# pca10036_sheet3_buttons_and_leds.net
KiCad netlist of a schematic drawn in Altium Designer
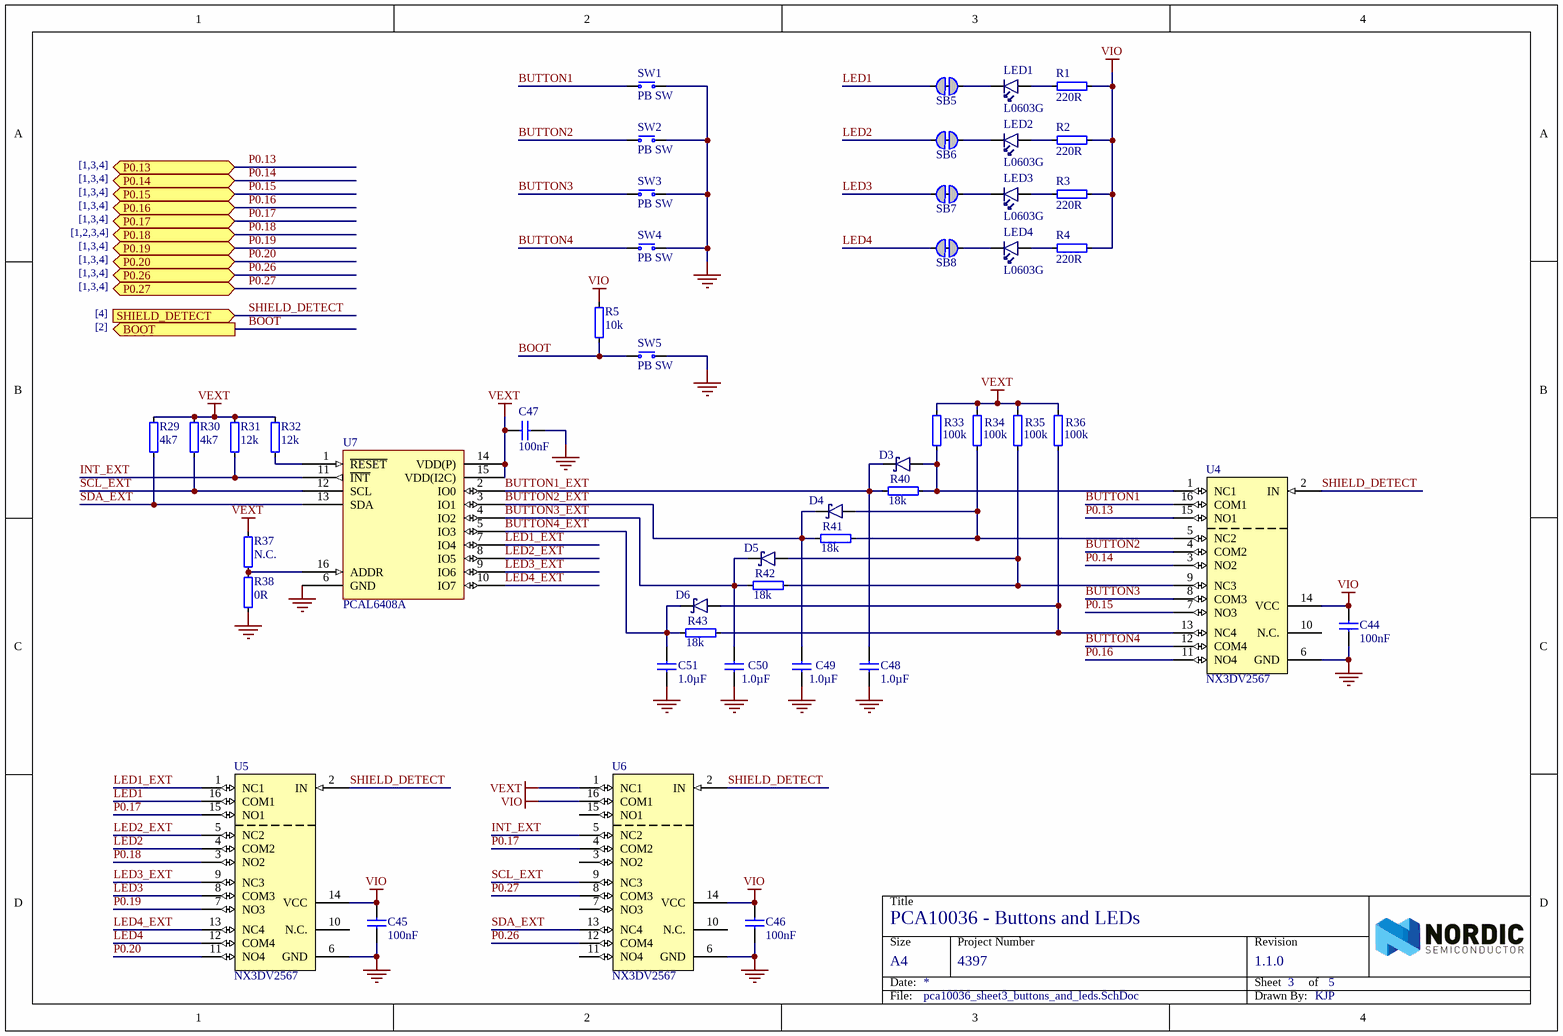
[diagram p0: pca10036_sheet3_buttons_and_leds.SchDoc]

(export (version "E")
  (design (tool "Eeschema 10.0.6"))
  (components
    (comp (ref "C44")
      (value "100nF")
      (footprint "CAPC1005X04L")
      (description "Capacitor, X7R, ±10%")
      (fields (field (name "PART NUMBER") "C0402-100n") (field (name "PUBLISHER") "Nordic Semiconductor"))
      (libsource (lib "Nordic Passive DB") (part "CAP"))
    )
    (comp (ref "C45")
      (value "100nF")
      (footprint "CAPC1005X04L")
      (description "Capacitor, X7R, ±10%")
      (fields (field (name "PART NUMBER") "C0402-100n") (field (name "PUBLISHER") "Nordic Semiconductor"))
      (libsource (lib "Nordic Passive DB") (part "CAP"))
    )
    (comp (ref "C46")
      (value "100nF")
      (footprint "CAPC1005X04L")
      (description "Capacitor, X7R, ±10%")
      (fields (field (name "PART NUMBER") "C0402-100n") (field (name "PUBLISHER") "Nordic Semiconductor"))
      (libsource (lib "Nordic Passive DB") (part "CAP"))
    )
    (comp (ref "C47")
      (value "100nF")
      (footprint "CAPC1005X04L")
      (description "Capacitor, X7R, ±10%")
      (fields (field (name "PART NUMBER") "C0402-100n") (field (name "PUBLISHER") "Nordic Semiconductor"))
      (libsource (lib "Nordic Passive DB") (part "CAP"))
    )
    (comp (ref "C48")
      (value "1.0µF")
      (footprint "CAPC1005X04L")
      (description "Capacitor, X5R, ±5%")
      (fields (field (name "PART NUMBER") "C0402-1µ0") (field (name "PUBLISHER") "Nordic Semiconductor"))
      (libsource (lib "Nordic Passive DB") (part "CAP"))
    )
    (comp (ref "C49")
      (value "1.0µF")
      (footprint "CAPC1005X04L")
      (description "Capacitor, X5R, ±5%")
      (fields (field (name "PART NUMBER") "C0402-1µ0") (field (name "PUBLISHER") "Nordic Semiconductor"))
      (libsource (lib "Nordic Passive DB") (part "CAP"))
    )
    (comp (ref "C50")
      (value "1.0µF")
      (footprint "CAPC1005X04L")
      (description "Capacitor, X5R, ±5%")
      (fields (field (name "PART NUMBER") "C0402-1µ0") (field (name "PUBLISHER") "Nordic Semiconductor"))
      (libsource (lib "Nordic Passive DB") (part "CAP"))
    )
    (comp (ref "C51")
      (value "1.0µF")
      (footprint "CAPC1005X04L")
      (description "Capacitor, X5R, ±5%")
      (fields (field (name "PART NUMBER") "C0402-1µ0") (field (name "PUBLISHER") "Nordic Semiconductor"))
      (libsource (lib "Nordic Passive DB") (part "CAP"))
    )
    (comp (ref "D3")
      (value "1PS79SB30.115")
      (footprint "SOD-523")
      (description "Diode Schottky Vf=0.38, Vr=40V, If=200mA, Ir=500nA")
      (fields (field (name "MANUFACTURER") "NXP") (field (name "PUBLISHER") "Nordic Semiconductor"))
      (libsource (lib "Nordic Discrete DB") (part "D{colon}SCHOTTKY"))
    )
    (comp (ref "D4")
      (value "1PS79SB30.115")
      (footprint "SOD-523")
      (description "Diode Schottky Vf=0.38, Vr=40V, If=200mA, Ir=500nA")
      (fields (field (name "MANUFACTURER") "NXP") (field (name "PUBLISHER") "Nordic Semiconductor"))
      (libsource (lib "Nordic Discrete DB") (part "D{colon}SCHOTTKY"))
    )
    (comp (ref "D5")
      (value "1PS79SB30.115")
      (footprint "SOD-523")
      (description "Diode Schottky Vf=0.38, Vr=40V, If=200mA, Ir=500nA")
      (fields (field (name "MANUFACTURER") "NXP") (field (name "PUBLISHER") "Nordic Semiconductor"))
      (libsource (lib "Nordic Discrete DB") (part "D{colon}SCHOTTKY"))
    )
    (comp (ref "D6")
      (value "1PS79SB30.115")
      (footprint "SOD-523")
      (description "Diode Schottky Vf=0.38, Vr=40V, If=200mA, Ir=500nA")
      (fields (field (name "MANUFACTURER") "NXP") (field (name "PUBLISHER") "Nordic Semiconductor"))
      (libsource (lib "Nordic Discrete DB") (part "D{colon}SCHOTTKY"))
    )
    (comp (ref "LED1")
      (value "L0603G")
      (footprint "LED_0603_G")
      (description "LED 0603, EL19-21SYGC")
      (fields
        (field (name "PART NUMBER") "EL19-21SYGC")
        (field (name "MANUFACTURER") "Everlight")
        (field (name "PUBLISHER") "Nordic Semiconductor")
      )
      (libsource (lib "Nordic Discrete DB") (part "D{colon}LED"))
    )
    (comp (ref "LED2")
      (value "L0603G")
      (footprint "LED_0603_G")
      (description "LED 0603, EL19-21SYGC")
      (fields
        (field (name "PART NUMBER") "EL19-21SYGC")
        (field (name "MANUFACTURER") "Everlight")
        (field (name "PUBLISHER") "Nordic Semiconductor")
      )
      (libsource (lib "Nordic Discrete DB") (part "D{colon}LED"))
    )
    (comp (ref "LED3")
      (value "L0603G")
      (footprint "LED_0603_G")
      (description "LED 0603, EL19-21SYGC")
      (fields
        (field (name "PART NUMBER") "EL19-21SYGC")
        (field (name "MANUFACTURER") "Everlight")
        (field (name "PUBLISHER") "Nordic Semiconductor")
      )
      (libsource (lib "Nordic Discrete DB") (part "D{colon}LED"))
    )
    (comp (ref "LED4")
      (value "L0603G")
      (footprint "LED_0603_G")
      (description "LED 0603, EL19-21SYGC")
      (fields
        (field (name "PART NUMBER") "EL19-21SYGC")
        (field (name "MANUFACTURER") "Everlight")
        (field (name "PUBLISHER") "Nordic Semiconductor")
      )
      (libsource (lib "Nordic Discrete DB") (part "D{colon}LED"))
    )
    (comp (ref "R1")
      (value "220R")
      (footprint "RESC1005X04L")
      (description "Resistor, ±1%, 0.063W")
      (fields (field (name "PART NUMBER") "R0402-220") (field (name "PUBLISHER") "Nordic Semiconductor"))
      (libsource (lib "Nordic Passive DB") (part "RES_1"))
    )
    (comp (ref "R2")
      (value "220R")
      (footprint "RESC1005X04L")
      (description "Resistor, ±1%, 0.063W")
      (fields (field (name "PART NUMBER") "R0402-220") (field (name "PUBLISHER") "Nordic Semiconductor"))
      (libsource (lib "Nordic Passive DB") (part "RES_1"))
    )
    (comp (ref "R3")
      (value "220R")
      (footprint "RESC1005X04L")
      (description "Resistor, ±1%, 0.063W")
      (fields (field (name "PART NUMBER") "R0402-220") (field (name "PUBLISHER") "Nordic Semiconductor"))
      (libsource (lib "Nordic Passive DB") (part "RES_1"))
    )
    (comp (ref "R4")
      (value "220R")
      (footprint "RESC1005X04L")
      (description "Resistor, ±1%, 0.063W")
      (fields (field (name "PART NUMBER") "R0402-220") (field (name "PUBLISHER") "Nordic Semiconductor"))
      (libsource (lib "Nordic Passive DB") (part "RES_1"))
    )
    (comp (ref "R5")
      (value "10k")
      (footprint "RESC1005X04L")
      (description "Resistor, ±1%, 0.063W")
      (fields (field (name "PART NUMBER") "R0402-10k") (field (name "PUBLISHER") "Nordic Semiconductor"))
      (libsource (lib "Nordic Passive DB") (part "RES_1"))
    )
    (comp (ref "R29")
      (value "4k7")
      (footprint "RESC1005X04L")
      (description "Resistor, ±1%, 0.063W")
      (fields (field (name "PART NUMBER") "R0402-4k7") (field (name "PUBLISHER") "Nordic Semiconductor"))
      (libsource (lib "Nordic Passive DB") (part "RES_1"))
    )
    (comp (ref "R30")
      (value "4k7")
      (footprint "RESC1005X04L")
      (description "Resistor, ±1%, 0.063W")
      (fields (field (name "PART NUMBER") "R0402-4k7") (field (name "PUBLISHER") "Nordic Semiconductor"))
      (libsource (lib "Nordic Passive DB") (part "RES_1"))
    )
    (comp (ref "R31")
      (value "12k")
      (footprint "RESC1005X04L")
      (description "Resistor, ±1%, 0.063W")
      (fields (field (name "PART NUMBER") "R0402-12k") (field (name "PUBLISHER") "Nordic Semiconductor"))
      (libsource (lib "Nordic Passive DB") (part "RES_1"))
    )
    (comp (ref "R32")
      (value "12k")
      (footprint "RESC1005X04L")
      (description "Resistor, ±1%, 0.063W")
      (fields (field (name "PART NUMBER") "R0402-12k") (field (name "PUBLISHER") "Nordic Semiconductor"))
      (libsource (lib "Nordic Passive DB") (part "RES_1"))
    )
    (comp (ref "R33")
      (value "100k")
      (footprint "RESC1005X04L")
      (description "Resistor, ±1%, 0.063W")
      (fields (field (name "PART NUMBER") "R0402-100k") (field (name "PUBLISHER") "Nordic Semiconductor"))
      (libsource (lib "Nordic Passive DB") (part "RES_1"))
    )
    (comp (ref "R34")
      (value "100k")
      (footprint "RESC1005X04L")
      (description "Resistor, ±1%, 0.063W")
      (fields (field (name "PART NUMBER") "R0402-100k") (field (name "PUBLISHER") "Nordic Semiconductor"))
      (libsource (lib "Nordic Passive DB") (part "RES_1"))
    )
    (comp (ref "R35")
      (value "100k")
      (footprint "RESC1005X04L")
      (description "Resistor, ±1%, 0.063W")
      (fields (field (name "PART NUMBER") "R0402-100k") (field (name "PUBLISHER") "Nordic Semiconductor"))
      (libsource (lib "Nordic Passive DB") (part "RES_1"))
    )
    (comp (ref "R36")
      (value "100k")
      (footprint "RESC1005X04L")
      (description "Resistor, ±1%, 0.063W")
      (fields (field (name "PART NUMBER") "R0402-100k") (field (name "PUBLISHER") "Nordic Semiconductor"))
      (libsource (lib "Nordic Passive DB") (part "RES_1"))
    )
    (comp (ref "R37")
      (value "N.C.")
      (footprint "RESC1005X04L")
      (description "Not mounted")
      (fields (field (name "PART NUMBER") "R0402-N.C.") (field (name "PUBLISHER") "Nordic Semiconductor"))
      (libsource (lib "Nordic Passive DB") (part "RES_1"))
    )
    (comp (ref "R38")
      (value "0R")
      (footprint "RESC1005X04L")
      (description "Resistor, ±5%, 0.063W")
      (fields (field (name "PART NUMBER") "R0402-0R") (field (name "PUBLISHER") "Nordic Semiconductor"))
      (libsource (lib "Nordic Passive DB") (part "RES_1"))
    )
    (comp (ref "R40")
      (value "18k")
      (footprint "RESC1005X04L")
      (description "Resistor, ±1%, 0.063W")
      (fields (field (name "PART NUMBER") "R0402-18k") (field (name "PUBLISHER") "Nordic Semiconductor"))
      (libsource (lib "Nordic Passive DB") (part "RES_1"))
    )
    (comp (ref "R41")
      (value "18k")
      (footprint "RESC1005X04L")
      (description "Resistor, ±1%, 0.063W")
      (fields (field (name "PART NUMBER") "R0402-18k") (field (name "PUBLISHER") "Nordic Semiconductor"))
      (libsource (lib "Nordic Passive DB") (part "RES_1"))
    )
    (comp (ref "R42")
      (value "18k")
      (footprint "RESC1005X04L")
      (description "Resistor, ±1%, 0.063W")
      (fields (field (name "PART NUMBER") "R0402-18k") (field (name "PUBLISHER") "Nordic Semiconductor"))
      (libsource (lib "Nordic Passive DB") (part "RES_1"))
    )
    (comp (ref "R43")
      (value "18k")
      (footprint "RESC1005X04L")
      (description "Resistor, ±1%, 0.063W")
      (fields (field (name "PART NUMBER") "R0402-18k") (field (name "PUBLISHER") "Nordic Semiconductor"))
      (libsource (lib "Nordic Passive DB") (part "RES_1"))
    )
    (comp (ref "SB5")
      (value "Solderbridge")
      (footprint "Solderbridge_Shorted")
      (description "Shorted Solderbridge")
      (fields
        (field (name "PART NUMBER") "Solderbridge Shorted")
        (field (name "PUBLISHER") "Nordic Semiconductor")
      )
      (libsource (lib "Nordic Passive DB") (part "SOLDERBRIDGE_SHORTED"))
    )
    (comp (ref "SB6")
      (value "Solderbridge")
      (footprint "Solderbridge_Shorted")
      (description "Shorted Solderbridge")
      (fields
        (field (name "PART NUMBER") "Solderbridge Shorted")
        (field (name "PUBLISHER") "Nordic Semiconductor")
      )
      (libsource (lib "Nordic Passive DB") (part "SOLDERBRIDGE_SHORTED"))
    )
    (comp (ref "SB7")
      (value "Solderbridge")
      (footprint "Solderbridge_Shorted")
      (description "Shorted Solderbridge")
      (fields
        (field (name "PART NUMBER") "Solderbridge Shorted")
        (field (name "PUBLISHER") "Nordic Semiconductor")
      )
      (libsource (lib "Nordic Passive DB") (part "SOLDERBRIDGE_SHORTED"))
    )
    (comp (ref "SB8")
      (value "Solderbridge")
      (footprint "Solderbridge_Shorted")
      (description "Shorted Solderbridge")
      (fields
        (field (name "PART NUMBER") "Solderbridge Shorted")
        (field (name "PUBLISHER") "Nordic Semiconductor")
      )
      (libsource (lib "Nordic Passive DB") (part "SOLDERBRIDGE_SHORTED"))
    )
    (comp (ref "SW1")
      (value "PB SW")
      (footprint "ALPS_SKHUxxx010_WO_GND")
      (description "ALPS - SKHUALE010 - Tactile Switch, SPNO, SMD, 6.5x6.2x2.5mm")
      (fields
        (field (name "PART NUMBER") "ALPS_SKHUALE010")
        (field (name "MANUFACTURER") "Alps")
        (field (name "PUBLISHER") "Nordic Semiconductor")
      )
      (libsource (lib "Nordic Discrete DB") (part "SW-PB"))
    )
    (comp (ref "SW2")
      (value "PB SW")
      (footprint "ALPS_SKHUxxx010_WO_GND")
      (description "ALPS - SKHUALE010 - Tactile Switch, SPNO, SMD, 6.5x6.2x2.5mm")
      (fields
        (field (name "PART NUMBER") "ALPS_SKHUALE010")
        (field (name "MANUFACTURER") "Alps")
        (field (name "PUBLISHER") "Nordic Semiconductor")
      )
      (libsource (lib "Nordic Discrete DB") (part "SW-PB"))
    )
    (comp (ref "SW3")
      (value "PB SW")
      (footprint "ALPS_SKHUxxx010_WO_GND")
      (description "ALPS - SKHUALE010 - Tactile Switch, SPNO, SMD, 6.5x6.2x2.5mm")
      (fields
        (field (name "PART NUMBER") "ALPS_SKHUALE010")
        (field (name "MANUFACTURER") "Alps")
        (field (name "PUBLISHER") "Nordic Semiconductor")
      )
      (libsource (lib "Nordic Discrete DB") (part "SW-PB"))
    )
    (comp (ref "SW4")
      (value "PB SW")
      (footprint "ALPS_SKHUxxx010_WO_GND")
      (description "ALPS - SKHUALE010 - Tactile Switch, SPNO, SMD, 6.5x6.2x2.5mm")
      (fields
        (field (name "PART NUMBER") "ALPS_SKHUALE010")
        (field (name "MANUFACTURER") "Alps")
        (field (name "PUBLISHER") "Nordic Semiconductor")
      )
      (libsource (lib "Nordic Discrete DB") (part "SW-PB"))
    )
    (comp (ref "SW5")
      (value "PB SW")
      (footprint "ALPS_SKHUxxx010_WO_GND")
      (description "ALPS - SKHUALE010 - Tactile Switch, SPNO, SMD, 6.5x6.2x2.5mm")
      (fields
        (field (name "PART NUMBER") "ALPS_SKHUALE010")
        (field (name "MANUFACTURER") "Alps")
        (field (name "PUBLISHER") "Nordic Semiconductor")
      )
      (libsource (lib "Nordic Discrete DB") (part "SW-PB"))
    )
    (comp (ref "U4")
      (value "NX3DV2567")
      (footprint "XQFN40P180X260X50-16N")
      (description "Low-ohmic four-pole double-throw analog switch")
      (fields
        (field (name "PART NUMBER") "NX3DV2567GU")
        (field (name "MANUFACTURER") "NXP Semiconductors")
        (field (name "PUBLISHER") "Nordic Semiconductor")
      )
      (libsource (lib "Nordic Active DB") (part "NX3DV2567"))
    )
    (comp (ref "U5")
      (value "NX3DV2567")
      (footprint "XQFN40P180X260X50-16N")
      (description "Low-ohmic four-pole double-throw analog switch")
      (fields
        (field (name "PART NUMBER") "NX3DV2567GU")
        (field (name "MANUFACTURER") "NXP Semiconductors")
        (field (name "PUBLISHER") "Nordic Semiconductor")
      )
      (libsource (lib "Nordic Active DB") (part "NX3DV2567"))
    )
    (comp (ref "U6")
      (value "NX3DV2567")
      (footprint "XQFN40P180X260X50-16N")
      (description "Low-ohmic four-pole double-throw analog switch")
      (fields
        (field (name "PART NUMBER") "NX3DV2567GU")
        (field (name "MANUFACTURER") "NXP Semiconductors")
        (field (name "PUBLISHER") "Nordic Semiconductor")
      )
      (libsource (lib "Nordic Active DB") (part "NX3DV2567"))
    )
    (comp (ref "U7")
      (value "PCAL6408A")
      (footprint "XQFN40P180X260X50-16N")
      (description "8-bit I2C-bus I/O expander with interrupt output")
      (fields
        (field (name "PART NUMBER") "PCAL6408AHK")
        (field (name "MANUFACTURER") "NXP Semiconductors")
        (field (name "PUBLISHER") "Nordic Semiconductor")
      )
      (libsource (lib "Nordic Active DB") (part "PCAL6408AHK"))
    )
  )
  (nets
    (net (code "1") (name "/BOOT") (class "Default")
      (node (ref "R5") (pin "1") (pinfunction "1_1") (pintype "passive"))
      (node (ref "SW5") (pin "1") (pinfunction "N.O_1") (pintype "passive"))
    )
    (net (code "2") (name "/BUTTON1") (class "Default")
      (node (ref "SW1") (pin "1") (pinfunction "N.O_1") (pintype "passive"))
      (node (ref "U4") (pin "16") (pinfunction "COM1_16") (pintype "bidirectional"))
    )
    (net (code "3") (name "/BUTTON1_EXT") (class "Default")
      (node (ref "C48") (pin "1") (pinfunction "1_1") (pintype "passive"))
      (node (ref "D3") (pin "3") (pinfunction "C_3") (pintype "passive"))
      (node (ref "R40") (pin "1") (pinfunction "1_1") (pintype "passive"))
      (node (ref "U7") (pin "2") (pinfunction "IO0_2") (pintype "bidirectional"))
    )
    (net (code "4") (name "/BUTTON2") (class "Default")
      (node (ref "SW2") (pin "1") (pinfunction "N.O_1") (pintype "passive"))
      (node (ref "U4") (pin "4") (pinfunction "COM2_4") (pintype "bidirectional"))
    )
    (net (code "5") (name "/BUTTON2_EXT") (class "Default")
      (node (ref "C49") (pin "2") (pinfunction "2_2") (pintype "passive"))
      (node (ref "D4") (pin "3") (pinfunction "C_3") (pintype "passive"))
      (node (ref "R41") (pin "1") (pinfunction "1_1") (pintype "passive"))
      (node (ref "U7") (pin "3") (pinfunction "IO1_3") (pintype "bidirectional"))
    )
    (net (code "6") (name "/BUTTON3") (class "Default")
      (node (ref "SW3") (pin "1") (pinfunction "N.O_1") (pintype "passive"))
      (node (ref "U4") (pin "8") (pinfunction "COM3_8") (pintype "bidirectional"))
    )
    (net (code "7") (name "/BUTTON3_EXT") (class "Default")
      (node (ref "C50") (pin "2") (pinfunction "2_2") (pintype "passive"))
      (node (ref "D5") (pin "3") (pinfunction "C_3") (pintype "passive"))
      (node (ref "R42") (pin "1") (pinfunction "1_1") (pintype "passive"))
      (node (ref "U7") (pin "4") (pinfunction "IO2_4") (pintype "bidirectional"))
    )
    (net (code "8") (name "/BUTTON4") (class "Default")
      (node (ref "SW4") (pin "1") (pinfunction "N.O_1") (pintype "passive"))
      (node (ref "U4") (pin "12") (pinfunction "COM4_12") (pintype "bidirectional"))
    )
    (net (code "9") (name "/BUTTON4_EXT") (class "Default")
      (node (ref "C51") (pin "1") (pinfunction "1_1") (pintype "passive"))
      (node (ref "D6") (pin "3") (pinfunction "C_3") (pintype "passive"))
      (node (ref "R43") (pin "1") (pinfunction "1_1") (pintype "passive"))
      (node (ref "U7") (pin "5") (pinfunction "IO3_5") (pintype "bidirectional"))
    )
    (net (code "10") (name "/INT_EXT") (class "Default")
      (node (ref "R31") (pin "1") (pinfunction "1_1") (pintype "passive"))
      (node (ref "U6") (pin "5") (pinfunction "NC2_5") (pintype "bidirectional"))
      (node (ref "U7") (pin "11") (pinfunction "~{INT}_11") (pintype "output"))
    )
    (net (code "11") (name "/LED1") (class "Default")
      (node (ref "SB5") (pin "1") (pinfunction "0_1") (pintype "passive"))
      (node (ref "U5") (pin "16") (pinfunction "COM1_16") (pintype "bidirectional"))
    )
    (net (code "12") (name "/LED1_EXT") (class "Default")
      (node (ref "U5") (pin "1") (pinfunction "NC1_1") (pintype "bidirectional"))
      (node (ref "U7") (pin "7") (pinfunction "IO4_7") (pintype "bidirectional"))
    )
    (net (code "13") (name "/LED2") (class "Default")
      (node (ref "SB6") (pin "1") (pinfunction "0_1") (pintype "passive"))
      (node (ref "U5") (pin "4") (pinfunction "COM2_4") (pintype "bidirectional"))
    )
    (net (code "14") (name "/LED2_EXT") (class "Default")
      (node (ref "U5") (pin "5") (pinfunction "NC2_5") (pintype "bidirectional"))
      (node (ref "U7") (pin "8") (pinfunction "IO5_8") (pintype "bidirectional"))
    )
    (net (code "15") (name "/LED3") (class "Default")
      (node (ref "SB7") (pin "1") (pinfunction "0_1") (pintype "passive"))
      (node (ref "U5") (pin "8") (pinfunction "COM3_8") (pintype "bidirectional"))
    )
    (net (code "16") (name "/LED3_EXT") (class "Default")
      (node (ref "U5") (pin "9") (pinfunction "NC3_9") (pintype "bidirectional"))
      (node (ref "U7") (pin "9") (pinfunction "IO6_9") (pintype "bidirectional"))
    )
    (net (code "17") (name "/LED4") (class "Default")
      (node (ref "SB8") (pin "1") (pinfunction "0_1") (pintype "passive"))
      (node (ref "U5") (pin "12") (pinfunction "COM4_12") (pintype "bidirectional"))
    )
    (net (code "18") (name "/LED4_EXT") (class "Default")
      (node (ref "U5") (pin "13") (pinfunction "NC4_13") (pintype "bidirectional"))
      (node (ref "U7") (pin "10") (pinfunction "IO7_10") (pintype "bidirectional"))
    )
    (net (code "19") (name "/P0.13") (class "Default")
      (node (ref "U4") (pin "15") (pinfunction "NO1_15") (pintype "bidirectional"))
    )
    (net (code "20") (name "/P0.14") (class "Default")
      (node (ref "U4") (pin "3") (pinfunction "NO2_3") (pintype "bidirectional"))
    )
    (net (code "21") (name "/P0.15") (class "Default")
      (node (ref "U4") (pin "7") (pinfunction "NO3_7") (pintype "bidirectional"))
    )
    (net (code "22") (name "/P0.16") (class "Default")
      (node (ref "U4") (pin "11") (pinfunction "NO4_11") (pintype "bidirectional"))
    )
    (net (code "23") (name "/P0.17") (class "Default")
      (node (ref "U5") (pin "15") (pinfunction "NO1_15") (pintype "bidirectional"))
      (node (ref "U6") (pin "4") (pinfunction "COM2_4") (pintype "bidirectional"))
    )
    (net (code "24") (name "/P0.18") (class "Default")
      (node (ref "U5") (pin "3") (pinfunction "NO2_3") (pintype "bidirectional"))
    )
    (net (code "25") (name "/P0.19") (class "Default")
      (node (ref "U5") (pin "7") (pinfunction "NO3_7") (pintype "bidirectional"))
    )
    (net (code "26") (name "/P0.20") (class "Default")
      (node (ref "U5") (pin "11") (pinfunction "NO4_11") (pintype "bidirectional"))
    )
    (net (code "27") (name "/P0.26") (class "Default")
      (node (ref "U6") (pin "12") (pinfunction "COM4_12") (pintype "bidirectional"))
    )
    (net (code "28") (name "/P0.27") (class "Default")
      (node (ref "U6") (pin "8") (pinfunction "COM3_8") (pintype "bidirectional"))
    )
    (net (code "29") (name "/SCL_EXT") (class "Default")
      (node (ref "R30") (pin "1") (pinfunction "1_1") (pintype "passive"))
      (node (ref "U6") (pin "9") (pinfunction "NC3_9") (pintype "bidirectional"))
      (node (ref "U7") (pin "12") (pinfunction "SCL_12") (pintype "power_in"))
    )
    (net (code "30") (name "/SDA_EXT") (class "Default")
      (node (ref "R29") (pin "1") (pinfunction "1_1") (pintype "passive"))
      (node (ref "U6") (pin "13") (pinfunction "NC4_13") (pintype "bidirectional"))
      (node (ref "U7") (pin "13") (pinfunction "SDA_13") (pintype "passive"))
    )
    (net (code "31") (name "/SHIELD_DETECT") (class "Default")
      (node (ref "U4") (pin "2") (pinfunction "IN_2") (pintype "input"))
      (node (ref "U5") (pin "2") (pinfunction "IN_2") (pintype "input"))
      (node (ref "U6") (pin "2") (pinfunction "IN_2") (pintype "input"))
    )
    (net (code "32") (name "GND") (class "Default")
      (node (ref "C44") (pin "1") (pinfunction "1_1") (pintype "passive"))
      (node (ref "C45") (pin "1") (pinfunction "1_1") (pintype "passive"))
      (node (ref "C46") (pin "1") (pinfunction "1_1") (pintype "passive"))
      (node (ref "C47") (pin "1") (pinfunction "1_1") (pintype "passive"))
      (node (ref "C48") (pin "2") (pinfunction "2_2") (pintype "passive"))
      (node (ref "C49") (pin "1") (pinfunction "1_1") (pintype "passive"))
      (node (ref "C50") (pin "1") (pinfunction "1_1") (pintype "passive"))
      (node (ref "C51") (pin "2") (pinfunction "2_2") (pintype "passive"))
      (node (ref "R38") (pin "1") (pinfunction "1_1") (pintype "passive"))
      (node (ref "SW1") (pin "2") (pinfunction "COM_2") (pintype "passive"))
      (node (ref "SW2") (pin "2") (pinfunction "COM_2") (pintype "passive"))
      (node (ref "SW3") (pin "2") (pinfunction "COM_2") (pintype "passive"))
      (node (ref "SW4") (pin "2") (pinfunction "COM_2") (pintype "passive"))
      (node (ref "SW5") (pin "2") (pinfunction "COM_2") (pintype "passive"))
      (node (ref "U4") (pin "6") (pinfunction "GND_6") (pintype "power_in"))
      (node (ref "U5") (pin "6") (pinfunction "GND_6") (pintype "power_in"))
      (node (ref "U6") (pin "6") (pinfunction "GND_6") (pintype "power_in"))
      (node (ref "U7") (pin "6") (pinfunction "GND_6") (pintype "power_in"))
    )
    (net (code "33") (name "Net-(D3-A)") (class "Default")
      (node (ref "D3") (pin "1") (pinfunction "A_1") (pintype "passive"))
      (node (ref "R33") (pin "1") (pinfunction "1_1") (pintype "passive"))
      (node (ref "R40") (pin "2") (pinfunction "2_2") (pintype "passive"))
      (node (ref "U4") (pin "1") (pinfunction "NC1_1") (pintype "bidirectional"))
    )
    (net (code "34") (name "Net-(D4-A)") (class "Default")
      (node (ref "D4") (pin "1") (pinfunction "A_1") (pintype "passive"))
      (node (ref "R34") (pin "1") (pinfunction "1_1") (pintype "passive"))
      (node (ref "R41") (pin "2") (pinfunction "2_2") (pintype "passive"))
      (node (ref "U4") (pin "5") (pinfunction "NC2_5") (pintype "bidirectional"))
    )
    (net (code "35") (name "Net-(D5-A)") (class "Default")
      (node (ref "D5") (pin "1") (pinfunction "A_1") (pintype "passive"))
      (node (ref "R35") (pin "1") (pinfunction "1_1") (pintype "passive"))
      (node (ref "R42") (pin "2") (pinfunction "2_2") (pintype "passive"))
      (node (ref "U4") (pin "9") (pinfunction "NC3_9") (pintype "bidirectional"))
    )
    (net (code "36") (name "Net-(D6-A)") (class "Default")
      (node (ref "D6") (pin "1") (pinfunction "A_1") (pintype "passive"))
      (node (ref "R36") (pin "1") (pinfunction "1_1") (pintype "passive"))
      (node (ref "R43") (pin "2") (pinfunction "2_2") (pintype "passive"))
      (node (ref "U4") (pin "13") (pinfunction "NC4_13") (pintype "bidirectional"))
    )
    (net (code "37") (name "Net-(LED1-A)") (class "Default")
      (node (ref "LED1") (pin "2") (pinfunction "A_2") (pintype "passive"))
      (node (ref "R1") (pin "1") (pinfunction "1_1") (pintype "passive"))
    )
    (net (code "38") (name "Net-(LED1-C)") (class "Default")
      (node (ref "LED1") (pin "1") (pinfunction "C_1") (pintype "passive"))
      (node (ref "SB5") (pin "2") (pinfunction "1_2") (pintype "passive"))
    )
    (net (code "39") (name "Net-(LED2-A)") (class "Default")
      (node (ref "LED2") (pin "2") (pinfunction "A_2") (pintype "passive"))
      (node (ref "R2") (pin "1") (pinfunction "1_1") (pintype "passive"))
    )
    (net (code "40") (name "Net-(LED2-C)") (class "Default")
      (node (ref "LED2") (pin "1") (pinfunction "C_1") (pintype "passive"))
      (node (ref "SB6") (pin "2") (pinfunction "1_2") (pintype "passive"))
    )
    (net (code "41") (name "Net-(LED3-A)") (class "Default")
      (node (ref "LED3") (pin "2") (pinfunction "A_2") (pintype "passive"))
      (node (ref "R3") (pin "1") (pinfunction "1_1") (pintype "passive"))
    )
    (net (code "42") (name "Net-(LED3-C)") (class "Default")
      (node (ref "LED3") (pin "1") (pinfunction "C_1") (pintype "passive"))
      (node (ref "SB7") (pin "2") (pinfunction "1_2") (pintype "passive"))
    )
    (net (code "43") (name "Net-(LED4-A)") (class "Default")
      (node (ref "LED4") (pin "2") (pinfunction "A_2") (pintype "passive"))
      (node (ref "R4") (pin "1") (pinfunction "1_1") (pintype "passive"))
    )
    (net (code "44") (name "Net-(LED4-C)") (class "Default")
      (node (ref "LED4") (pin "1") (pinfunction "C_1") (pintype "passive"))
      (node (ref "SB8") (pin "2") (pinfunction "1_2") (pintype "passive"))
    )
    (net (code "45") (name "Net-(U7-ADDR)") (class "Default")
      (node (ref "R37") (pin "1") (pinfunction "1_1") (pintype "passive"))
      (node (ref "R38") (pin "2") (pinfunction "2_2") (pintype "passive"))
      (node (ref "U7") (pin "16") (pinfunction "ADDR_16") (pintype "input"))
    )
    (net (code "46") (name "Net-(U7-~{RESET})") (class "Default")
      (node (ref "R32") (pin "1") (pinfunction "1_1") (pintype "passive"))
      (node (ref "U7") (pin "1") (pinfunction "~{RESET}_1") (pintype "input"))
    )
    (net (code "47") (name "VEXT") (class "Default")
      (node (ref "C47") (pin "2") (pinfunction "2_2") (pintype "passive"))
      (node (ref "R29") (pin "2") (pinfunction "2_2") (pintype "passive"))
      (node (ref "R30") (pin "2") (pinfunction "2_2") (pintype "passive"))
      (node (ref "R31") (pin "2") (pinfunction "2_2") (pintype "passive"))
      (node (ref "R32") (pin "2") (pinfunction "2_2") (pintype "passive"))
      (node (ref "R33") (pin "2") (pinfunction "2_2") (pintype "passive"))
      (node (ref "R34") (pin "2") (pinfunction "2_2") (pintype "passive"))
      (node (ref "R35") (pin "2") (pinfunction "2_2") (pintype "passive"))
      (node (ref "R36") (pin "2") (pinfunction "2_2") (pintype "passive"))
      (node (ref "R37") (pin "2") (pinfunction "2_2") (pintype "passive"))
      (node (ref "U6") (pin "1") (pinfunction "NC1_1") (pintype "bidirectional"))
      (node (ref "U7") (pin "14") (pinfunction "VDD(P)_14") (pintype "power_in"))
      (node (ref "U7") (pin "15") (pinfunction "VDD(I2C)_15") (pintype "power_in"))
    )
    (net (code "48") (name "VIO") (class "Default")
      (node (ref "C44") (pin "2") (pinfunction "2_2") (pintype "passive"))
      (node (ref "C45") (pin "2") (pinfunction "2_2") (pintype "passive"))
      (node (ref "C46") (pin "2") (pinfunction "2_2") (pintype "passive"))
      (node (ref "R1") (pin "2") (pinfunction "2_2") (pintype "passive"))
      (node (ref "R2") (pin "2") (pinfunction "2_2") (pintype "passive"))
      (node (ref "R3") (pin "2") (pinfunction "2_2") (pintype "passive"))
      (node (ref "R4") (pin "2") (pinfunction "2_2") (pintype "passive"))
      (node (ref "R5") (pin "2") (pinfunction "2_2") (pintype "passive"))
      (node (ref "U4") (pin "14") (pinfunction "VCC_14") (pintype "power_in"))
      (node (ref "U5") (pin "14") (pinfunction "VCC_14") (pintype "power_in"))
      (node (ref "U6") (pin "14") (pinfunction "VCC_14") (pintype "power_in"))
      (node (ref "U6") (pin "16") (pinfunction "COM1_16") (pintype "bidirectional"))
    )
    (net (code "49") (name "unconnected-(U4-N.C.-Pad10)") (class "Default")
      (node (ref "U4") (pin "10") (pinfunction "N.C._10") (pintype "passive"))
    )
    (net (code "50") (name "unconnected-(U5-N.C.-Pad10)") (class "Default")
      (node (ref "U5") (pin "10") (pinfunction "N.C._10") (pintype "passive"))
    )
    (net (code "51") (name "unconnected-(U6-N.C.-Pad10)") (class "Default")
      (node (ref "U6") (pin "10") (pinfunction "N.C._10") (pintype "passive"))
    )
    (net (code "52") (name "unconnected-(U6-NO1-Pad15)") (class "Default")
      (node (ref "U6") (pin "15") (pinfunction "NO1_15") (pintype "bidirectional"))
    )
    (net (code "53") (name "unconnected-(U6-NO2-Pad3)") (class "Default")
      (node (ref "U6") (pin "3") (pinfunction "NO2_3") (pintype "bidirectional"))
    )
    (net (code "54") (name "unconnected-(U6-NO3-Pad7)") (class "Default")
      (node (ref "U6") (pin "7") (pinfunction "NO3_7") (pintype "bidirectional"))
    )
    (net (code "55") (name "unconnected-(U6-NO4-Pad11)") (class "Default")
      (node (ref "U6") (pin "11") (pinfunction "NO4_11") (pintype "bidirectional"))
    )
  )
)
